# arduinoDcc1_3.net
KiCad netlist of a schematic drawn in EAGLE
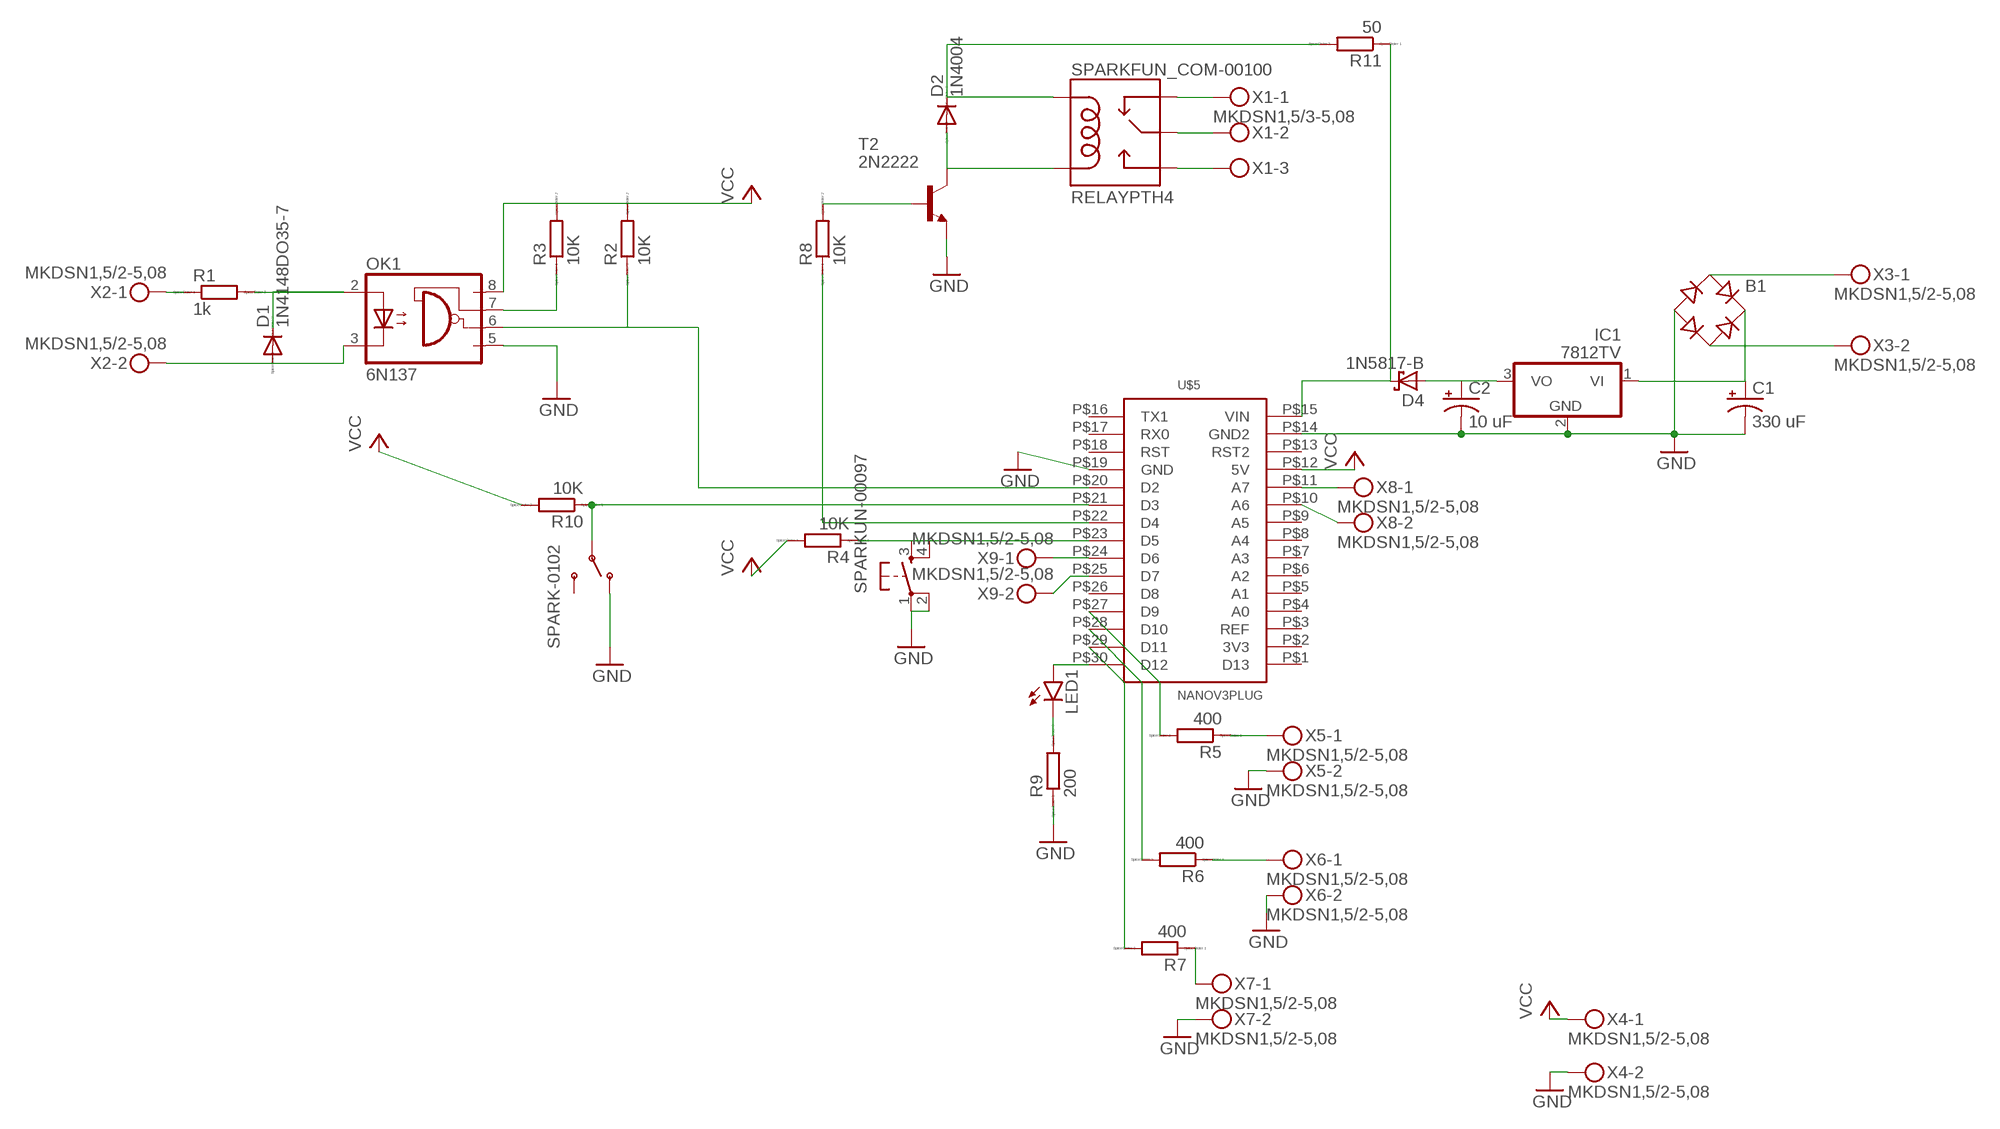
[diagram p0: schematic, sheet 1]

(export (version "E")
  (design (tool "Eeschema 10.0.6"))
  (components
    (comp (ref "B1")
      (value "RB1A")
      (footprint "eagle-import:RB1A")
      (libsource (lib "eagle-import") (part "RB1A"))
    )
    (comp (ref "C1")
      (value "330 uF")
      (footprint "eagle-import:CPOL-RADIAL-100UF-25V")
      (libsource (lib "eagle-import") (part "CAP_POLPTH1"))
    )
    (comp (ref "C2")
      (value "10 uF")
      (footprint "eagle-import:CPOL-RADIAL-100UF-25V")
      (libsource (lib "eagle-import") (part "CAP_POLPTH1"))
    )
    (comp (ref "D1")
      (value "1N4148DO35-7")
      (footprint "eagle-import:DO35-7")
      (libsource (lib "eagle-import") (part "1N4148DO35-7"))
    )
    (comp (ref "D2")
      (value "1N4004")
      (footprint "eagle-import:DO41-10")
      (libsource (lib "eagle-import") (part "1N4004"))
    )
    (comp (ref "D4")
      (value "1N5817-B")
      (footprint "eagle-import:DO41-7.6")
      (libsource (lib "eagle-import") (part "1N5817-B"))
    )
    (comp (ref "IC1")
      (value "7812TV")
      (footprint "eagle-import:TO220V")
      (libsource (lib "eagle-import") (part "78TV12"))
    )
    (comp (ref "LED1")
      (value "LED3MM")
      (footprint "eagle-import:LED3MM")
      (libsource (lib "eagle-import") (part "LED3MM"))
    )
    (comp (ref "OK1")
      (value "6N137")
      (footprint "eagle-import:DIL08")
      (libsource (lib "eagle-import") (part "6N137"))
    )
    (comp (ref "R1")
      (value "1k")
      (footprint "eagle-import:0207_10")
      (libsource (lib "eagle-import") (part "R0207/10"))
    )
    (comp (ref "R2")
      (value "10K")
      (footprint "eagle-import:0207_10")
      (libsource (lib "eagle-import") (part "R0207/10"))
    )
    (comp (ref "R3")
      (value "10K")
      (footprint "eagle-import:0207_10")
      (libsource (lib "eagle-import") (part "R0207/10"))
    )
    (comp (ref "R4")
      (value "10K")
      (footprint "eagle-import:0207_10")
      (libsource (lib "eagle-import") (part "R0207/10"))
    )
    (comp (ref "R5")
      (value "400")
      (footprint "eagle-import:0207_10")
      (libsource (lib "eagle-import") (part "R0207/10"))
    )
    (comp (ref "R6")
      (value "400")
      (footprint "eagle-import:0207_10")
      (libsource (lib "eagle-import") (part "R0207/10"))
    )
    (comp (ref "R7")
      (value "400")
      (footprint "eagle-import:0207_10")
      (libsource (lib "eagle-import") (part "R0207/10"))
    )
    (comp (ref "R8")
      (value "10K")
      (footprint "eagle-import:0207_10")
      (libsource (lib "eagle-import") (part "R0207/10"))
    )
    (comp (ref "R9")
      (value "200")
      (footprint "eagle-import:0204_7")
      (libsource (lib "eagle-import") (part "R0204/7"))
    )
    (comp (ref "R10")
      (value "10K")
      (footprint "eagle-import:0207_10")
      (libsource (lib "eagle-import") (part "R0207/10"))
    )
    (comp (ref "R11")
      (value "50")
      (footprint "eagle-import:0207_10")
      (libsource (lib "eagle-import") (part "R0207/10"))
    )
    (comp (ref "SPARK-0102")
      (value "SWITCH-SPDTPTH")
      (footprint "eagle-import:SWITCH-SPDT")
      (libsource (lib "eagle-import") (part "SWITCH-SPDTPTH"))
    )
    (comp (ref "SPARKFUN_COM-00100")
      (value "RELAYPTH4")
      (footprint "eagle-import:RELAY-JZC")
      (libsource (lib "eagle-import") (part "RELAYPTH4"))
    )
    (comp (ref "SPARKUN-00097")
      (value "TAC_SWITCHPTH")
      (footprint "eagle-import:TACTILE-PTH")
      (libsource (lib "eagle-import") (part "TAC_SWITCHPTH"))
    )
    (comp (ref "T2")
      (value "2N2222")
      (footprint "eagle-import:TO18")
      (libsource (lib "eagle-import") (part "2N2222"))
    )
    (comp (ref "U$5")
      (value "NANOV3PLUG")
      (footprint "eagle-import:HEADER15-2")
      (libsource (lib "eagle-import") (part "NANOV3PLUG"))
    )
    (comp (ref "X1")
      (value "MKDSN1,5/3-5,08")
      (footprint "eagle-import:MKDSN1,5_3-5,08")
      (libsource (lib "eagle-import") (part "MKDSN1,5/3-5,08"))
    )
    (comp (ref "X2")
      (value "MKDSN1,5/2-5,08")
      (footprint "eagle-import:MKDSN1,5_2-5,08")
      (libsource (lib "eagle-import") (part "MKDSN1,5/2-5,08"))
    )
    (comp (ref "X3")
      (value "MKDSN1,5/2-5,08")
      (footprint "eagle-import:MKDSN1,5_2-5,08")
      (libsource (lib "eagle-import") (part "MKDSN1,5/2-5,08"))
    )
    (comp (ref "X4")
      (value "MKDSN1,5/2-5,08")
      (footprint "eagle-import:MKDSN1,5_2-5,08")
      (libsource (lib "eagle-import") (part "MKDSN1,5/2-5,08"))
    )
    (comp (ref "X5")
      (value "MKDSN1,5/2-5,08")
      (footprint "eagle-import:MKDSN1,5_2-5,08")
      (libsource (lib "eagle-import") (part "MKDSN1,5/2-5,08"))
    )
    (comp (ref "X6")
      (value "MKDSN1,5/2-5,08")
      (footprint "eagle-import:MKDSN1,5_2-5,08")
      (libsource (lib "eagle-import") (part "MKDSN1,5/2-5,08"))
    )
    (comp (ref "X7")
      (value "MKDSN1,5/2-5,08")
      (footprint "eagle-import:MKDSN1,5_2-5,08")
      (libsource (lib "eagle-import") (part "MKDSN1,5/2-5,08"))
    )
    (comp (ref "X8")
      (value "MKDSN1,5/2-5,08")
      (footprint "eagle-import:MKDSN1,5_2-5,08")
      (libsource (lib "eagle-import") (part "MKDSN1,5/2-5,08"))
    )
    (comp (ref "X9")
      (value "MKDSN1,5/2-5,08")
      (footprint "eagle-import:MKDSN1,5_2-5,08")
      (libsource (lib "eagle-import") (part "MKDSN1,5/2-5,08"))
    )
  )
  (nets
    (net (code "1") (name "GND") (class "Default")
      (node (ref "B1") (pin "-") (pinfunction "-_-") (pintype "passive"))
      (node (ref "C1") (pin "2") (pinfunction "-_2") (pintype "passive"))
      (node (ref "C2") (pin "2") (pinfunction "-_2") (pintype "passive"))
      (node (ref "IC1") (pin "2") (pinfunction "GND_2") (pintype "passive"))
      (node (ref "OK1") (pin "5") (pinfunction "GND_5") (pintype "passive"))
      (node (ref "R9") (pin "1") (pinfunction "1_1") (pintype "passive"))
      (node (ref "SPARK-0102") (pin "1") (pinfunction "O_1") (pintype "passive"))
      (node (ref "SPARKUN-00097") (pin "1") (pinfunction "1_1") (pintype "passive"))
      (node (ref "SPARKUN-00097") (pin "2") (pinfunction "2_2") (pintype "passive"))
      (node (ref "T2") (pin "1") (pinfunction "E_1") (pintype "passive"))
      (node (ref "U$5") (pin "P$14") (pinfunction "GND2_P$14") (pintype "bidirectional"))
      (node (ref "U$5") (pin "P$19") (pinfunction "GND_P$19") (pintype "bidirectional"))
      (node (ref "X4") (pin "2") (pinfunction "KL_2") (pintype "passive"))
      (node (ref "X5") (pin "2") (pinfunction "KL_2") (pintype "passive"))
      (node (ref "X6") (pin "2") (pinfunction "KL_2") (pintype "passive"))
      (node (ref "X7") (pin "2") (pinfunction "KL_2") (pintype "passive"))
    )
    (net (code "2") (name "Net-(C1-+)") (class "Default")
      (node (ref "B1") (pin "+") (pinfunction "+_+") (pintype "passive"))
      (node (ref "C1") (pin "1") (pinfunction "+_1") (pintype "passive"))
      (node (ref "IC1") (pin "1") (pinfunction "VI_1") (pintype "input"))
    )
    (net (code "3") (name "Net-(C2-+)") (class "Default")
      (node (ref "C2") (pin "1") (pinfunction "+_1") (pintype "passive"))
      (node (ref "D4") (pin "A") (pinfunction "A_A") (pintype "passive"))
      (node (ref "IC1") (pin "3") (pinfunction "VO_3") (pintype "passive"))
    )
    (net (code "4") (name "Net-(LED1-C)") (class "Default")
      (node (ref "LED1") (pin "K") (pinfunction "C_K") (pintype "passive"))
      (node (ref "R9") (pin "2") (pinfunction "2_2") (pintype "passive"))
    )
    (net (code "5") (name "Net-(OK1-A)") (class "Default")
      (node (ref "D1") (pin "C") (pinfunction "C_C") (pintype "passive"))
      (node (ref "OK1") (pin "2") (pinfunction "A_2") (pintype "passive"))
      (node (ref "R1") (pin "2") (pinfunction "2_2") (pintype "passive"))
    )
    (net (code "6") (name "Net-(OK1-C)") (class "Default")
      (node (ref "D1") (pin "A") (pinfunction "A_A") (pintype "passive"))
      (node (ref "OK1") (pin "3") (pinfunction "C_3") (pintype "passive"))
      (node (ref "X2") (pin "2") (pinfunction "KL_2") (pintype "passive"))
    )
    (net (code "7") (name "Net-(OK1-VE)") (class "Default")
      (node (ref "OK1") (pin "7") (pinfunction "VE_7") (pintype "passive"))
      (node (ref "R3") (pin "1") (pinfunction "1_1") (pintype "passive"))
    )
    (net (code "8") (name "Net-(OK1-VO)") (class "Default")
      (node (ref "OK1") (pin "6") (pinfunction "VO_6") (pintype "passive"))
      (node (ref "R2") (pin "1") (pinfunction "1_1") (pintype "passive"))
      (node (ref "U$5") (pin "P$20") (pinfunction "D2_P$20") (pintype "bidirectional"))
    )
    (net (code "9") (name "Net-(SPARK-0102-P)") (class "Default")
      (node (ref "R10") (pin "1") (pinfunction "1_1") (pintype "passive"))
      (node (ref "SPARK-0102") (pin "2") (pinfunction "P_2") (pintype "passive"))
      (node (ref "U$5") (pin "P$21") (pinfunction "D3_P$21") (pintype "bidirectional"))
    )
    (net (code "10") (name "Net-(SPARKFUN_COM-00100-COIL1)") (class "Default")
      (node (ref "D2") (pin "C") (pinfunction "C_C") (pintype "passive"))
      (node (ref "R11") (pin "2") (pinfunction "2_2") (pintype "passive"))
      (node (ref "SPARKFUN_COM-00100") (pin "5") (pinfunction "COIL1_5") (pintype "bidirectional"))
    )
    (net (code "11") (name "Net-(SPARKFUN_COM-00100-COIL2)") (class "Default")
      (node (ref "D2") (pin "A") (pinfunction "A_A") (pintype "passive"))
      (node (ref "SPARKFUN_COM-00100") (pin "1") (pinfunction "COIL2_1") (pintype "bidirectional"))
      (node (ref "T2") (pin "3") (pinfunction "C_3") (pintype "passive"))
    )
    (net (code "12") (name "Net-(SPARKFUN_COM-00100-MAIN)") (class "Default")
      (node (ref "SPARKFUN_COM-00100") (pin "4") (pinfunction "MAIN_4") (pintype "bidirectional"))
      (node (ref "X1") (pin "2") (pinfunction "KL_2") (pintype "passive"))
    )
    (net (code "13") (name "Net-(SPARKFUN_COM-00100-NC)") (class "Default")
      (node (ref "SPARKFUN_COM-00100") (pin "2") (pinfunction "NC_2") (pintype "bidirectional"))
      (node (ref "X1") (pin "1") (pinfunction "KL_1") (pintype "passive"))
    )
    (net (code "14") (name "Net-(SPARKFUN_COM-00100-NO)") (class "Default")
      (node (ref "SPARKFUN_COM-00100") (pin "3") (pinfunction "NO_3") (pintype "bidirectional"))
      (node (ref "X1") (pin "3") (pinfunction "KL_3") (pintype "passive"))
    )
    (net (code "15") (name "Net-(T2-B)") (class "Default")
      (node (ref "R8") (pin "2") (pinfunction "2_2") (pintype "passive"))
      (node (ref "T2") (pin "2") (pinfunction "B_2") (pintype "passive"))
    )
    (net (code "16") (name "Net-(U$5-A6)") (class "Default")
      (node (ref "U$5") (pin "P$10") (pinfunction "A6_P$10") (pintype "bidirectional"))
      (node (ref "X8") (pin "2") (pinfunction "KL_2") (pintype "passive"))
    )
    (net (code "17") (name "Net-(U$5-A7)") (class "Default")
      (node (ref "U$5") (pin "P$11") (pinfunction "A7_P$11") (pintype "bidirectional"))
      (node (ref "X8") (pin "1") (pinfunction "KL_1") (pintype "passive"))
    )
    (net (code "18") (name "Net-(U$5-D4)") (class "Default")
      (node (ref "R8") (pin "1") (pinfunction "1_1") (pintype "passive"))
      (node (ref "U$5") (pin "P$22") (pinfunction "D4_P$22") (pintype "bidirectional"))
    )
    (net (code "19") (name "Net-(U$5-D5)") (class "Default")
      (node (ref "R4") (pin "1") (pinfunction "1_1") (pintype "passive"))
      (node (ref "SPARKUN-00097") (pin "3") (pinfunction "3_3") (pintype "passive"))
      (node (ref "SPARKUN-00097") (pin "4") (pinfunction "4_4") (pintype "passive"))
      (node (ref "U$5") (pin "P$23") (pinfunction "D5_P$23") (pintype "bidirectional"))
    )
    (net (code "20") (name "Net-(U$5-D6)") (class "Default")
      (node (ref "U$5") (pin "P$24") (pinfunction "D6_P$24") (pintype "bidirectional"))
      (node (ref "X9") (pin "1") (pinfunction "KL_1") (pintype "passive"))
    )
    (net (code "21") (name "Net-(U$5-D7)") (class "Default")
      (node (ref "U$5") (pin "P$25") (pinfunction "D7_P$25") (pintype "bidirectional"))
      (node (ref "X9") (pin "2") (pinfunction "KL_2") (pintype "passive"))
    )
    (net (code "22") (name "Net-(U$5-D9)") (class "Default")
      (node (ref "R5") (pin "2") (pinfunction "2_2") (pintype "passive"))
      (node (ref "U$5") (pin "P$27") (pinfunction "D9_P$27") (pintype "bidirectional"))
    )
    (net (code "23") (name "Net-(U$5-D10)") (class "Default")
      (node (ref "R6") (pin "2") (pinfunction "2_2") (pintype "passive"))
      (node (ref "U$5") (pin "P$28") (pinfunction "D10_P$28") (pintype "bidirectional"))
    )
    (net (code "24") (name "Net-(U$5-D11)") (class "Default")
      (node (ref "R7") (pin "2") (pinfunction "2_2") (pintype "passive"))
      (node (ref "U$5") (pin "P$29") (pinfunction "D11_P$29") (pintype "bidirectional"))
    )
    (net (code "25") (name "Net-(U$5-D12)") (class "Default")
      (node (ref "LED1") (pin "A") (pinfunction "A_A") (pintype "passive"))
      (node (ref "U$5") (pin "P$30") (pinfunction "D12_P$30") (pintype "bidirectional"))
    )
    (net (code "26") (name "Net-(U$5-VIN)") (class "Default")
      (node (ref "D4") (pin "C") (pinfunction "C_C") (pintype "passive"))
      (node (ref "R11") (pin "1") (pinfunction "1_1") (pintype "passive"))
      (node (ref "U$5") (pin "P$15") (pinfunction "VIN_P$15") (pintype "bidirectional"))
    )
    (net (code "27") (name "Net-(X2A-KL)") (class "Default")
      (node (ref "R1") (pin "1") (pinfunction "1_1") (pintype "passive"))
      (node (ref "X2") (pin "1") (pinfunction "KL_1") (pintype "passive"))
    )
    (net (code "28") (name "Net-(X3A-KL)") (class "Default")
      (node (ref "B1") (pin "AC1") (pinfunction "AC1_AC1") (pintype "passive"))
      (node (ref "X3") (pin "1") (pinfunction "KL_1") (pintype "passive"))
    )
    (net (code "29") (name "Net-(X3B-KL)") (class "Default")
      (node (ref "B1") (pin "AC2") (pinfunction "AC2_AC2") (pintype "passive"))
      (node (ref "X3") (pin "2") (pinfunction "KL_2") (pintype "passive"))
    )
    (net (code "30") (name "Net-(X5A-KL)") (class "Default")
      (node (ref "R5") (pin "1") (pinfunction "1_1") (pintype "passive"))
      (node (ref "X5") (pin "1") (pinfunction "KL_1") (pintype "passive"))
    )
    (net (code "31") (name "Net-(X6A-KL)") (class "Default")
      (node (ref "R6") (pin "1") (pinfunction "1_1") (pintype "passive"))
      (node (ref "X6") (pin "1") (pinfunction "KL_1") (pintype "passive"))
    )
    (net (code "32") (name "Net-(X7A-KL)") (class "Default")
      (node (ref "R7") (pin "1") (pinfunction "1_1") (pintype "passive"))
      (node (ref "X7") (pin "1") (pinfunction "KL_1") (pintype "passive"))
    )
    (net (code "33") (name "VCC") (class "Default")
      (node (ref "OK1") (pin "8") (pinfunction "VCC_8") (pintype "passive"))
      (node (ref "R10") (pin "2") (pinfunction "2_2") (pintype "passive"))
      (node (ref "R2") (pin "2") (pinfunction "2_2") (pintype "passive"))
      (node (ref "R3") (pin "2") (pinfunction "2_2") (pintype "passive"))
      (node (ref "R4") (pin "2") (pinfunction "2_2") (pintype "passive"))
      (node (ref "U$5") (pin "P$12") (pinfunction "5V_P$12") (pintype "bidirectional"))
      (node (ref "X4") (pin "1") (pinfunction "KL_1") (pintype "passive"))
    )
    (net (code "34") (name "unconnected-(SPARK-0102-S-Pad3)") (class "Default")
      (node (ref "SPARK-0102") (pin "3") (pinfunction "S_3") (pintype "passive"))
    )
    (net (code "35") (name "unconnected-(U$5-3V3-PadP$2)") (class "Default")
      (node (ref "U$5") (pin "P$2") (pinfunction "3V3_P$2") (pintype "bidirectional"))
    )
    (net (code "36") (name "unconnected-(U$5-A0-PadP$4)") (class "Default")
      (node (ref "U$5") (pin "P$4") (pinfunction "A0_P$4") (pintype "bidirectional"))
    )
    (net (code "37") (name "unconnected-(U$5-A1-PadP$5)") (class "Default")
      (node (ref "U$5") (pin "P$5") (pinfunction "A1_P$5") (pintype "bidirectional"))
    )
    (net (code "38") (name "unconnected-(U$5-A2-PadP$6)") (class "Default")
      (node (ref "U$5") (pin "P$6") (pinfunction "A2_P$6") (pintype "bidirectional"))
    )
    (net (code "39") (name "unconnected-(U$5-A3-PadP$7)") (class "Default")
      (node (ref "U$5") (pin "P$7") (pinfunction "A3_P$7") (pintype "bidirectional"))
    )
    (net (code "40") (name "unconnected-(U$5-A4-PadP$8)") (class "Default")
      (node (ref "U$5") (pin "P$8") (pinfunction "A4_P$8") (pintype "bidirectional"))
    )
    (net (code "41") (name "unconnected-(U$5-A5-PadP$9)") (class "Default")
      (node (ref "U$5") (pin "P$9") (pinfunction "A5_P$9") (pintype "bidirectional"))
    )
    (net (code "42") (name "unconnected-(U$5-D8-PadP$26)") (class "Default")
      (node (ref "U$5") (pin "P$26") (pinfunction "D8_P$26") (pintype "bidirectional"))
    )
    (net (code "43") (name "unconnected-(U$5-D13-PadP$1)") (class "Default")
      (node (ref "U$5") (pin "P$1") (pinfunction "D13_P$1") (pintype "bidirectional"))
    )
    (net (code "44") (name "unconnected-(U$5-REF-PadP$3)") (class "Default")
      (node (ref "U$5") (pin "P$3") (pinfunction "REF_P$3") (pintype "bidirectional"))
    )
    (net (code "45") (name "unconnected-(U$5-RST-PadP$18)") (class "Default")
      (node (ref "U$5") (pin "P$18") (pinfunction "RST_P$18") (pintype "bidirectional"))
    )
    (net (code "46") (name "unconnected-(U$5-RST2-PadP$13)") (class "Default")
      (node (ref "U$5") (pin "P$13") (pinfunction "RST2_P$13") (pintype "bidirectional"))
    )
    (net (code "47") (name "unconnected-(U$5-RX0-PadP$17)") (class "Default")
      (node (ref "U$5") (pin "P$17") (pinfunction "RX0_P$17") (pintype "bidirectional"))
    )
    (net (code "48") (name "unconnected-(U$5-TX1-PadP$16)") (class "Default")
      (node (ref "U$5") (pin "P$16") (pinfunction "TX1_P$16") (pintype "bidirectional"))
    )
  )
)
